# 3_ADSTM32-Pheripherial.net
KiCad netlist of a schematic drawn in Altium Designer
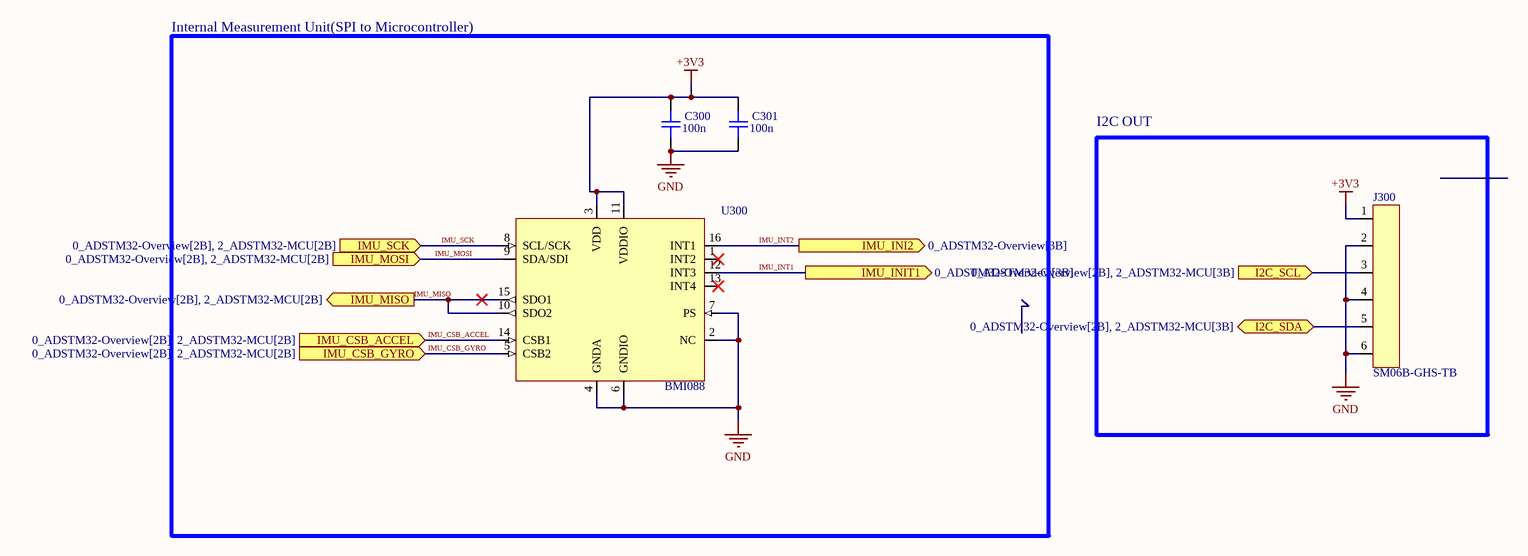
[diagram p0: 3_ADSTM32-Pheripherial.SchDoc]

(export (version "E")
  (design (tool "Eeschema 10.0.6"))
  (components
    (comp (ref "C300")
      (value "100n")
      (footprint "CAP_0603")
      (description "Capacitor SMD 0603 16V")
      (libsource (lib "Schematic-Lib-PhilsLab") (part "CAP_0603_16V"))
    )
    (comp (ref "C301")
      (value "100n")
      (footprint "CAP_0603")
      (description "Capacitor SMD 0603 16V")
      (libsource (lib "Schematic-Lib-PhilsLab") (part "CAP_0603_16V"))
    )
    (comp (ref "J300")
      (value "SM06B-GHS-TB")
      (footprint "SM06B-GHS-TB")
      (description "Header Connector 6 Position 1.25MM Pitch SMD Horizontal JST GH")
      (fields (field (name "MANUFACTURER") "JST"))
      (libsource (lib "Schematic-Lib-PhilsLab") (part "SM06B-GHS-TB"))
    )
    (comp (ref "U300")
      (value "BMI088")
      (footprint "BMI088")
      (description "Inertial Measurement Unit IMU 6-Axis LGA")
      (fields (field (name "MANUFACTURER") "Bosch"))
      (libsource (lib "Schematic-Lib-PhilsLab") (part "BMI088"))
    )
  )
  (nets
    (net (code "1") (name "+3V3") (class "Default")
      (node (ref "C300") (pin "2") (pinfunction "2_2") (pintype "passive"))
      (node (ref "C301") (pin "2") (pinfunction "2_2") (pintype "passive"))
      (node (ref "J300") (pin "1") (pinfunction "1_1") (pintype "passive"))
      (node (ref "U300") (pin "11") (pinfunction "VDDIO_11") (pintype "power_in"))
      (node (ref "U300") (pin "3") (pinfunction "VDD_3") (pintype "power_in"))
    )
    (net (code "2") (name "/I2C_SCL") (class "Default")
      (node (ref "J300") (pin "3") (pinfunction "3_3") (pintype "passive"))
    )
    (net (code "3") (name "/I2C_SDA") (class "Default")
      (node (ref "J300") (pin "5") (pinfunction "5_5") (pintype "passive"))
    )
    (net (code "4") (name "/IMU_CSB_ACCEL") (class "Default")
      (node (ref "U300") (pin "14") (pinfunction "CSB1_14") (pintype "input"))
    )
    (net (code "5") (name "/IMU_CSB_GYRO") (class "Default")
      (node (ref "U300") (pin "5") (pinfunction "CSB2_5") (pintype "input"))
    )
    (net (code "6") (name "/IMU_INT1") (class "Default")
      (node (ref "U300") (pin "12") (pinfunction "INT3_12") (pintype "bidirectional"))
    )
    (net (code "7") (name "/IMU_INT2") (class "Default")
      (node (ref "U300") (pin "16") (pinfunction "INT1_16") (pintype "bidirectional"))
    )
    (net (code "8") (name "/IMU_MISO") (class "Default")
      (node (ref "U300") (pin "10") (pinfunction "SDO2_10") (pintype "output"))
      (node (ref "U300") (pin "15") (pinfunction "SDO1_15") (pintype "output"))
    )
    (net (code "9") (name "/IMU_MOSI") (class "Default")
      (node (ref "U300") (pin "9") (pinfunction "SDA/SDI_9") (pintype "bidirectional"))
    )
    (net (code "10") (name "/IMU_SCK") (class "Default")
      (node (ref "U300") (pin "8") (pinfunction "SCL/SCK_8") (pintype "input"))
    )
    (net (code "11") (name "GND") (class "Default")
      (node (ref "C300") (pin "1") (pinfunction "1_1") (pintype "passive"))
      (node (ref "C301") (pin "1") (pinfunction "1_1") (pintype "passive"))
      (node (ref "J300") (pin "2") (pinfunction "2_2") (pintype "passive"))
      (node (ref "J300") (pin "4") (pinfunction "4_4") (pintype "passive"))
      (node (ref "J300") (pin "6") (pinfunction "6_6") (pintype "passive"))
      (node (ref "U300") (pin "2") (pinfunction "NC_2") (pintype "passive"))
      (node (ref "U300") (pin "4") (pinfunction "GNDA_4") (pintype "power_in"))
      (node (ref "U300") (pin "6") (pinfunction "GNDIO_6") (pintype "power_in"))
      (node (ref "U300") (pin "7") (pinfunction "PS_7") (pintype "input"))
    )
    (net (code "12") (name "unconnected-(U300-INT2-Pad1)") (class "Default")
      (node (ref "U300") (pin "1") (pinfunction "INT2_1") (pintype "bidirectional+no_connect"))
    )
    (net (code "13") (name "unconnected-(U300-INT4-Pad13)") (class "Default")
      (node (ref "U300") (pin "13") (pinfunction "INT4_13") (pintype "bidirectional+no_connect"))
    )
  )
)
